# AudioJack.net
KiCad netlist of a schematic drawn in EAGLE
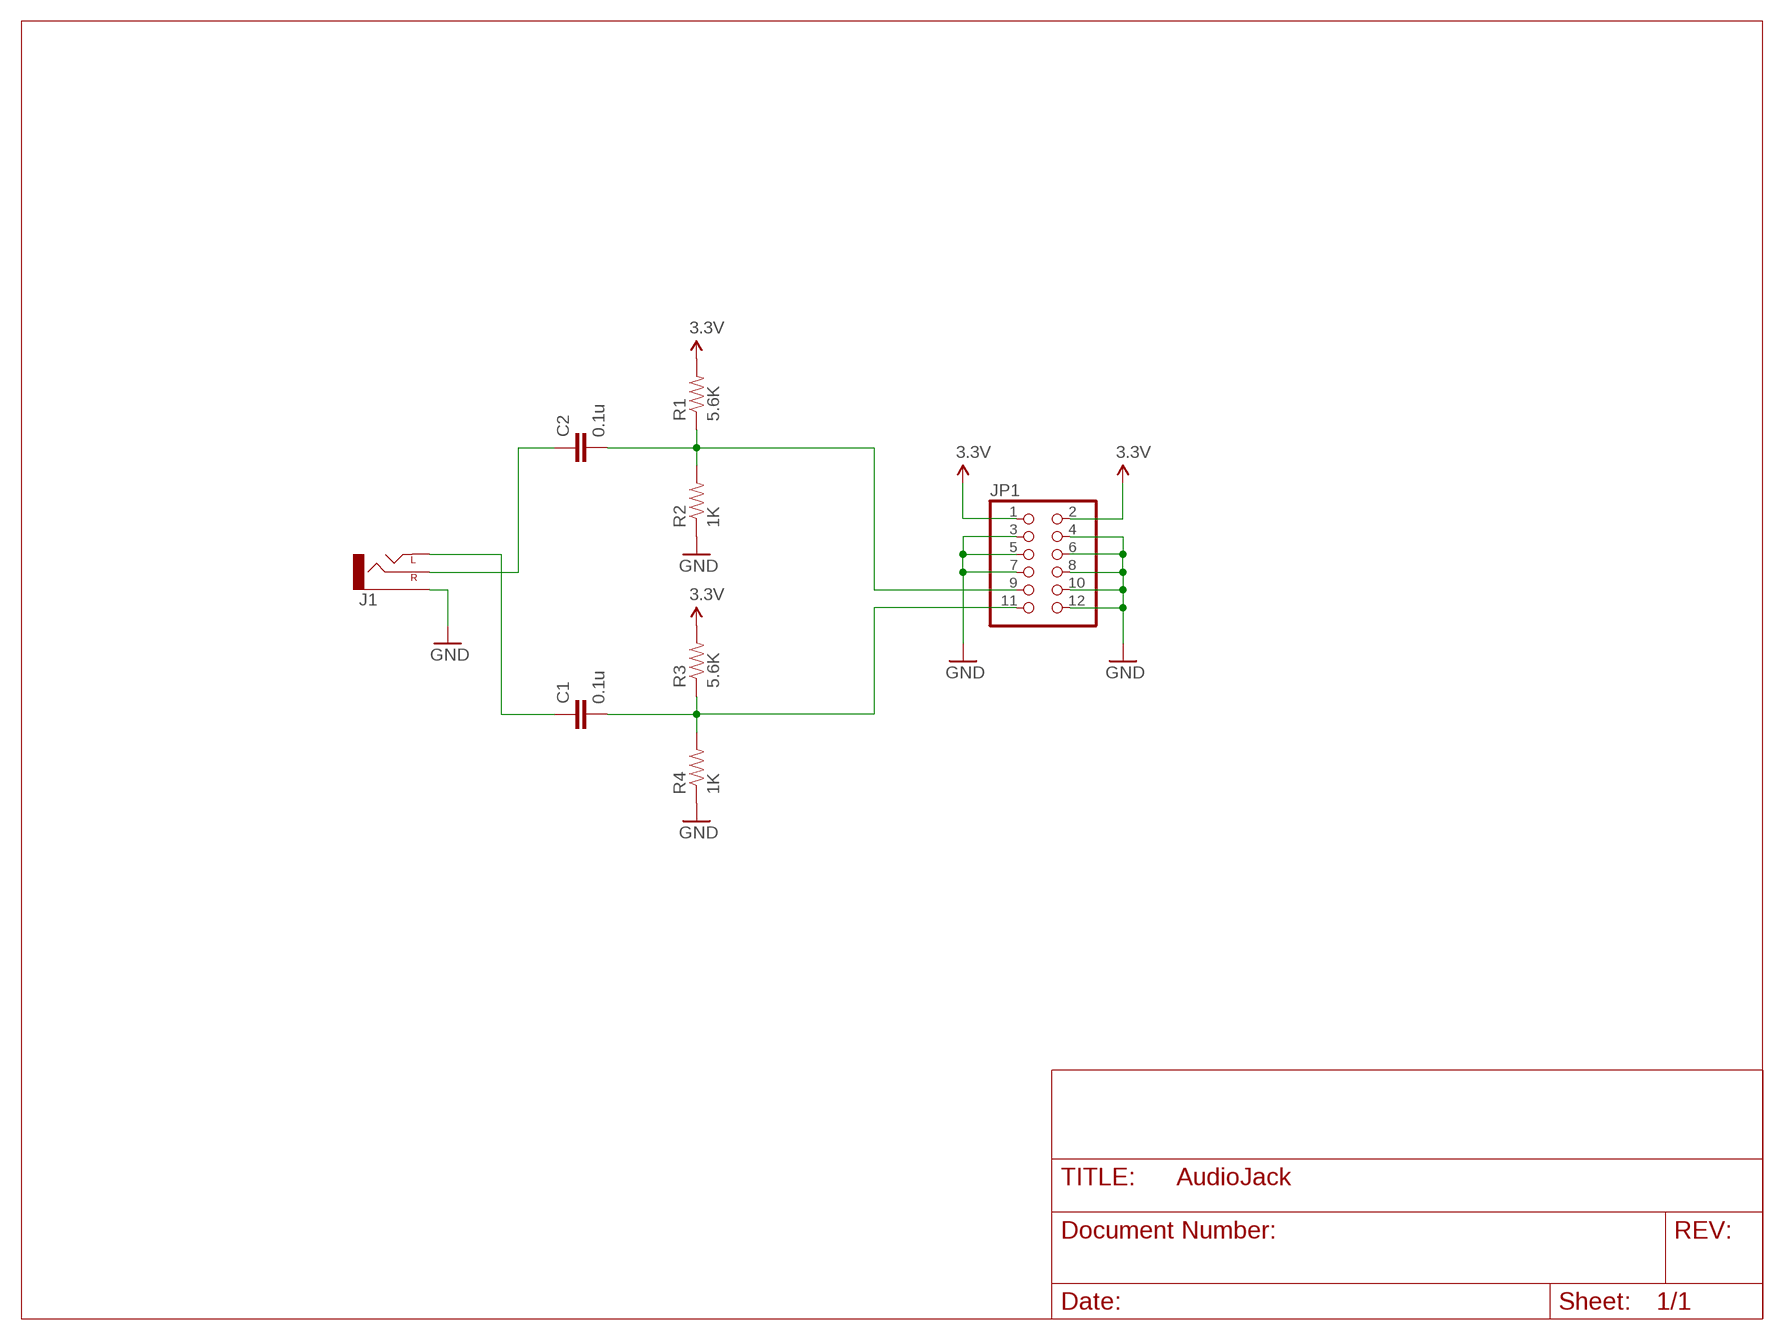
[diagram p0: schematic, sheet 1]

(export (version "E")
  (design (tool "Eeschema 10.0.6"))
  (components
    (comp (ref "C1")
      (value "0.1u")
      (footprint "eagle-import:CAP-PTH-5MM")
      (libsource (lib "eagle-import") (part "CAPPTH1"))
    )
    (comp (ref "C2")
      (value "0.1u")
      (footprint "eagle-import:CAP-PTH-5MM")
      (libsource (lib "eagle-import") (part "CAPPTH1"))
    )
    (comp (ref "J1")
      (value "AUDIO-JACKPTH")
      (footprint "eagle-import:AUDIO-JACK")
      (libsource (lib "eagle-import") (part "AUDIO-JACKPTH"))
    )
    (comp (ref "JP1")
      (value "PINHD-2X6/90")
      (footprint "eagle-import:2X06_90")
      (libsource (lib "eagle-import") (part "PINHD-2X6/90"))
    )
    (comp (ref "R1")
      (value "5.6K")
      (footprint "eagle-import:AXIAL-0.4")
      (libsource (lib "eagle-import") (part "RESISTORPTH-1/4W"))
    )
    (comp (ref "R2")
      (value "1K")
      (footprint "eagle-import:AXIAL-0.4")
      (libsource (lib "eagle-import") (part "RESISTORPTH-1/4W"))
    )
    (comp (ref "R3")
      (value "5.6K")
      (footprint "eagle-import:AXIAL-0.4")
      (libsource (lib "eagle-import") (part "RESISTORPTH-1/4W"))
    )
    (comp (ref "R4")
      (value "1K")
      (footprint "eagle-import:AXIAL-0.4")
      (libsource (lib "eagle-import") (part "RESISTORPTH-1/4W"))
    )
  )
  (nets
    (net (code "1") (name "3.3V") (class "Default")
      (node (ref "JP1") (pin "1") (pinfunction "1_1") (pintype "passive"))
      (node (ref "JP1") (pin "2") (pinfunction "2_2") (pintype "passive"))
      (node (ref "R1") (pin "P$2") (pinfunction "2_P$2") (pintype "passive"))
      (node (ref "R3") (pin "P$2") (pinfunction "2_P$2") (pintype "passive"))
    )
    (net (code "2") (name "GND") (class "Default")
      (node (ref "J1") (pin "SLEEVE") (pinfunction "SLEEVE_SLEEVE") (pintype "bidirectional"))
      (node (ref "JP1") (pin "10") (pinfunction "10_10") (pintype "passive"))
      (node (ref "JP1") (pin "12") (pinfunction "12_12") (pintype "passive"))
      (node (ref "JP1") (pin "3") (pinfunction "3_3") (pintype "passive"))
      (node (ref "JP1") (pin "4") (pinfunction "4_4") (pintype "passive"))
      (node (ref "JP1") (pin "5") (pinfunction "5_5") (pintype "passive"))
      (node (ref "JP1") (pin "6") (pinfunction "6_6") (pintype "passive"))
      (node (ref "JP1") (pin "7") (pinfunction "7_7") (pintype "passive"))
      (node (ref "JP1") (pin "8") (pinfunction "8_8") (pintype "passive"))
      (node (ref "R2") (pin "P$1") (pinfunction "1_P$1") (pintype "passive"))
      (node (ref "R4") (pin "P$1") (pinfunction "1_P$1") (pintype "passive"))
    )
    (net (code "3") (name "Net-(J1-LEFT)") (class "Default")
      (node (ref "C1") (pin "1") (pinfunction "1_1") (pintype "passive"))
      (node (ref "J1") (pin "TIP") (pinfunction "LEFT_TIP") (pintype "bidirectional"))
    )
    (net (code "4") (name "Net-(J1-RIGHT)") (class "Default")
      (node (ref "C2") (pin "1") (pinfunction "1_1") (pintype "passive"))
      (node (ref "J1") (pin "RING") (pinfunction "RIGHT_RING") (pintype "bidirectional"))
    )
    (net (code "5") (name "Net-(R1-1)") (class "Default")
      (node (ref "C2") (pin "2") (pinfunction "2_2") (pintype "passive"))
      (node (ref "JP1") (pin "9") (pinfunction "9_9") (pintype "passive"))
      (node (ref "R1") (pin "P$1") (pinfunction "1_P$1") (pintype "passive"))
      (node (ref "R2") (pin "P$2") (pinfunction "2_P$2") (pintype "passive"))
    )
    (net (code "6") (name "Net-(R3-1)") (class "Default")
      (node (ref "C1") (pin "2") (pinfunction "2_2") (pintype "passive"))
      (node (ref "JP1") (pin "11") (pinfunction "11_11") (pintype "passive"))
      (node (ref "R3") (pin "P$1") (pinfunction "1_P$1") (pintype "passive"))
      (node (ref "R4") (pin "P$2") (pinfunction "2_P$2") (pintype "passive"))
    )
  )
)
